# 15-MT7688AN_Ethernet-E.net
KiCad netlist of a schematic drawn in Altium Designer
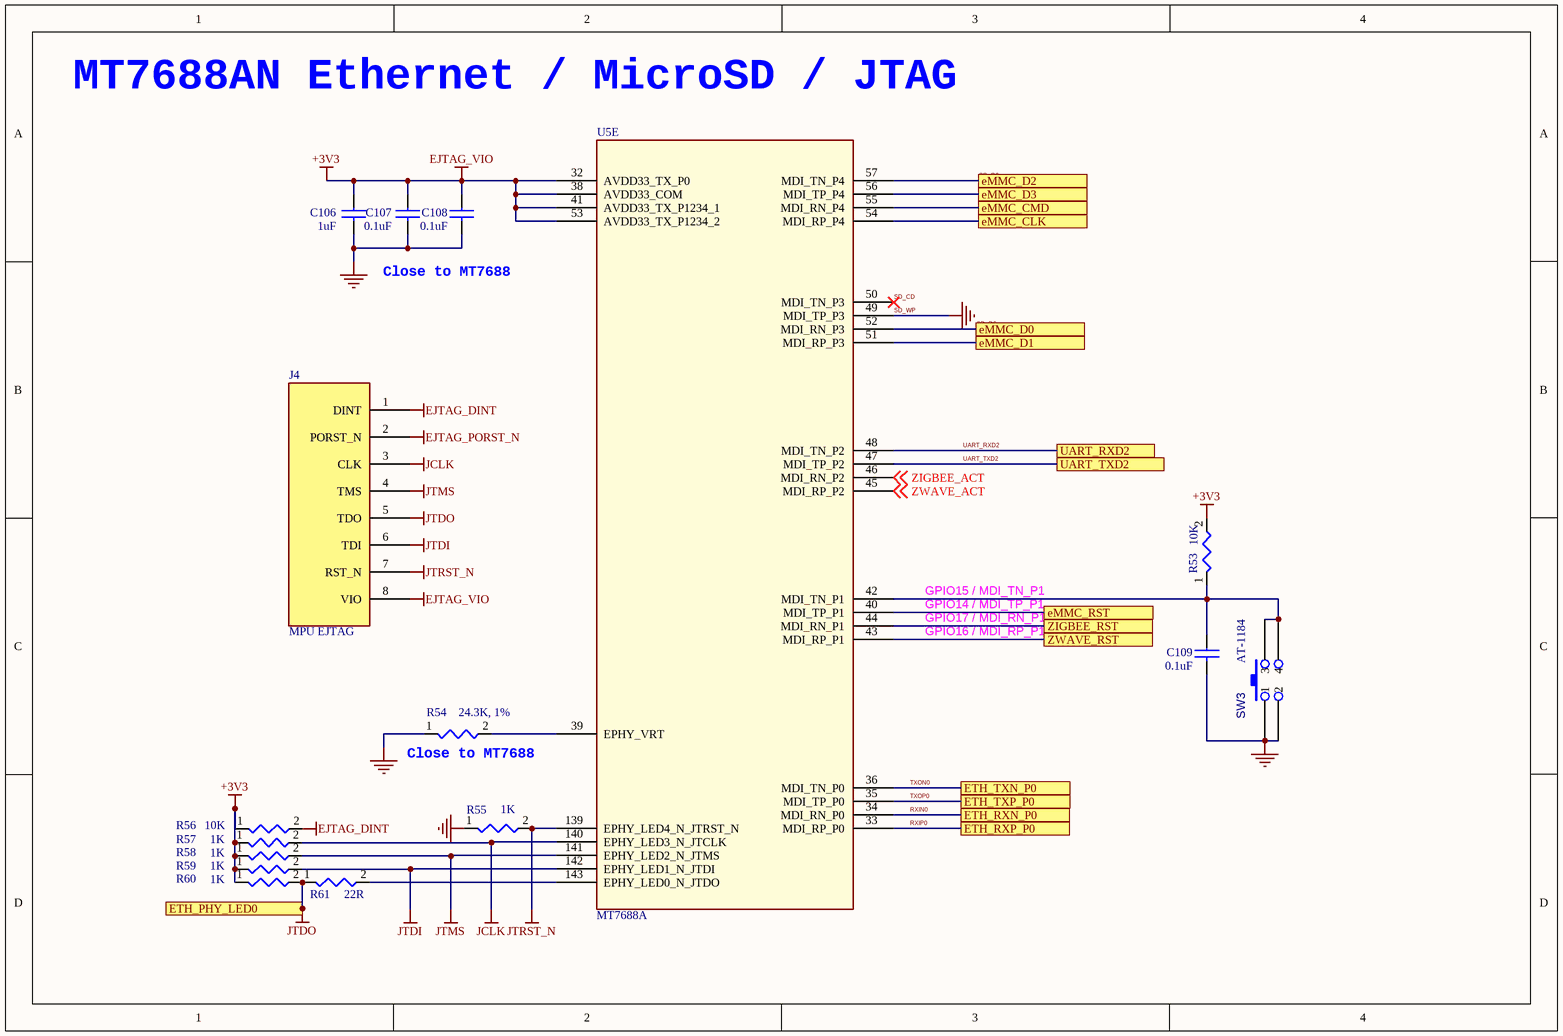
[diagram p0: 15-MT7688AN Ethernet-E.SchDoc]

(export (version "E")
  (design (tool "Eeschema 10.0.6"))
  (components
    (comp (ref "C106")
      (value "1uF")
      (footprint "CAPC1005X60X30NL05T10")
      (libsource (lib "MT7688AN") (part "CAP NP"))
    )
    (comp (ref "C107")
      (value "0.1uF")
      (footprint "CAPC1005X60X30NL05T10")
      (libsource (lib "MT7688AN") (part "CAP NP"))
    )
    (comp (ref "C108")
      (value "0.1uF")
      (footprint "CAPC1005X60X30NL05T10")
      (libsource (lib "MT7688AN") (part "CAP NP"))
    )
    (comp (ref "C109")
      (value "0.1uF")
      (footprint "CAPC1005X60X30NL05T10")
      (libsource (lib "MT7688AN") (part "CAP NP"))
    )
    (comp (ref "J4")
      (value "MPU EJTAG")
      (footprint "MPU EJTAG DEBUG")
      (libsource (lib "MT7688AN") (part "MPU EJTAG"))
    )
    (comp (ref "R53")
      (value "10K")
      (footprint "RESC1005X35X25NL10T10")
      (libsource (lib "MT7688AN") (part "RES/0402_3"))
    )
    (comp (ref "R54")
      (value "24.3K, 1%")
      (footprint "RESC1005X35X25NL10T10")
      (libsource (lib "MT7688AN") (part "RES/0402_3"))
    )
    (comp (ref "R55")
      (value "1K")
      (footprint "RESC1005X35X25NL10T10")
      (libsource (lib "MT7688AN") (part "RES/0402_3"))
    )
    (comp (ref "R56")
      (value "10K")
      (footprint "RESC1005X35X25NL10T10")
      (libsource (lib "MT7688AN") (part "RES/0402_3"))
    )
    (comp (ref "R57")
      (value "1K")
      (footprint "RESC1005X35X25NL10T10")
      (libsource (lib "MT7688AN") (part "RES/0402_3"))
    )
    (comp (ref "R58")
      (value "1K")
      (footprint "RESC1005X35X25NL10T10")
      (libsource (lib "MT7688AN") (part "RES/0402_3"))
    )
    (comp (ref "R59")
      (value "1K")
      (footprint "RESC1005X35X25NL10T10")
      (libsource (lib "MT7688AN") (part "RES/0402_3"))
    )
    (comp (ref "R60")
      (value "1K")
      (footprint "RESC1005X35X25NL10T10")
      (libsource (lib "MT7688AN") (part "RES/0402_3"))
    )
    (comp (ref "R61")
      (value "22R")
      (footprint "RESC1005X35X25NL10T10")
      (libsource (lib "MT7688AN") (part "RES/0402_3"))
    )
    (comp (ref "SW3")
      (value "AT-1184")
      (footprint "AT-1184 SW")
      (description "TACT Switch, H=1.5mm")
      (fields (field (name "MANUFACTURER") "Panasonic - ECG"))
      (libsource (lib "MT7688AN") (part "SW"))
    )
    (comp (ref "U5")
      (value "MT7688A")
      (footprint "MT7628AN$2F$DRQFN156$2F$SMD$2F$P0.5$2F$12X12")
      (libsource (lib "MT7688AN") (part "MT7620N-n_26"))
    )
  )
  (nets
    (net (code "1") (name "+3V3") (class "Default")
      (node (ref "C106") (pin "1") (pinfunction "1_1") (pintype "passive"))
      (node (ref "C107") (pin "1") (pinfunction "1_1") (pintype "passive"))
      (node (ref "C108") (pin "1") (pinfunction "1_1") (pintype "passive"))
      (node (ref "J4") (pin "8") (pinfunction "VIO_8") (pintype "passive"))
      (node (ref "R53") (pin "2") (pinfunction "2_2") (pintype "passive"))
      (node (ref "R56") (pin "1") (pinfunction "1_1") (pintype "passive"))
      (node (ref "R57") (pin "1") (pinfunction "1_1") (pintype "passive"))
      (node (ref "R58") (pin "1") (pinfunction "1_1") (pintype "passive"))
      (node (ref "R59") (pin "1") (pinfunction "1_1") (pintype "passive"))
      (node (ref "R60") (pin "1") (pinfunction "1_1") (pintype "passive"))
      (node (ref "U5") (pin "32") (pinfunction "AVDD33_TX_P0_32") (pintype "power_in"))
      (node (ref "U5") (pin "38") (pinfunction "AVDD33_COM_38") (pintype "power_in"))
      (node (ref "U5") (pin "41") (pinfunction "AVDD33_TX_P1234_1_41") (pintype "power_in"))
      (node (ref "U5") (pin "53") (pinfunction "AVDD33_TX_P1234_2_53") (pintype "power_in"))
    )
    (net (code "2") (name "/GPIO14 {slash} MDI_TP_P1") (class "Default")
      (node (ref "U5") (pin "40") (pinfunction "MDI_TP_P1_40") (pintype "passive"))
    )
    (net (code "3") (name "/GPIO15 {slash} MDI_TN_P1") (class "Default")
      (node (ref "C109") (pin "1") (pinfunction "1_1") (pintype "passive"))
      (node (ref "R53") (pin "1") (pinfunction "1_1") (pintype "passive"))
      (node (ref "SW3") (pin "3") (pinfunction "3_3") (pintype "passive"))
      (node (ref "SW3") (pin "4") (pinfunction "4_4") (pintype "passive"))
      (node (ref "U5") (pin "42") (pinfunction "MDI_TN_P1_42") (pintype "passive"))
    )
    (net (code "4") (name "/GPIO16 {slash} MDI_RP_P1") (class "Default")
      (node (ref "U5") (pin "43") (pinfunction "MDI_RP_P1_43") (pintype "passive"))
    )
    (net (code "5") (name "/GPIO17 {slash} MDI_RN_P1") (class "Default")
      (node (ref "U5") (pin "44") (pinfunction "MDI_RN_P1_44") (pintype "passive"))
    )
    (net (code "6") (name "/RXIN0") (class "Default")
      (node (ref "U5") (pin "34") (pinfunction "MDI_RN_P0_34") (pintype "passive"))
    )
    (net (code "7") (name "/RXIP0") (class "Default")
      (node (ref "U5") (pin "33") (pinfunction "MDI_RP_P0_33") (pintype "passive"))
    )
    (net (code "8") (name "/SD_CD") (class "Default")
      (node (ref "U5") (pin "50") (pinfunction "MDI_TN_P3_50") (pintype "passive+no_connect"))
    )
    (net (code "9") (name "/SD_CLK") (class "Default")
      (node (ref "U5") (pin "54") (pinfunction "MDI_RP_P4_54") (pintype "passive"))
    )
    (net (code "10") (name "/SD_CMD") (class "Default")
      (node (ref "U5") (pin "55") (pinfunction "MDI_RN_P4_55") (pintype "passive"))
    )
    (net (code "11") (name "/SD_D0") (class "Default")
      (node (ref "U5") (pin "52") (pinfunction "MDI_RN_P3_52") (pintype "passive"))
    )
    (net (code "12") (name "/SD_D1") (class "Default")
      (node (ref "U5") (pin "51") (pinfunction "MDI_RP_P3_51") (pintype "passive"))
    )
    (net (code "13") (name "/SD_D2") (class "Default")
      (node (ref "U5") (pin "57") (pinfunction "MDI_TN_P4_57") (pintype "passive"))
    )
    (net (code "14") (name "/SD_D3") (class "Default")
      (node (ref "U5") (pin "56") (pinfunction "MDI_TP_P4_56") (pintype "passive"))
    )
    (net (code "15") (name "/TXON0") (class "Default")
      (node (ref "U5") (pin "36") (pinfunction "MDI_TN_P0_36") (pintype "passive"))
    )
    (net (code "16") (name "/TXOP0") (class "Default")
      (node (ref "U5") (pin "35") (pinfunction "MDI_TP_P0_35") (pintype "passive"))
    )
    (net (code "17") (name "/UART_RXD2") (class "Default")
      (node (ref "U5") (pin "48") (pinfunction "MDI_TN_P2_48") (pintype "passive"))
    )
    (net (code "18") (name "/UART_TXD2") (class "Default")
      (node (ref "U5") (pin "47") (pinfunction "MDI_TP_P2_47") (pintype "passive"))
    )
    (net (code "19") (name "EJTAG_DINT") (class "Default")
      (node (ref "J4") (pin "1") (pinfunction "DINT_1") (pintype "passive"))
      (node (ref "R56") (pin "2") (pinfunction "2_2") (pintype "passive"))
    )
    (net (code "20") (name "EJTAG_PORST_N") (class "Default")
      (node (ref "J4") (pin "2") (pinfunction "PORST_N_2") (pintype "passive"))
    )
    (net (code "21") (name "GND") (class "Default")
      (node (ref "C106") (pin "2") (pinfunction "2_2") (pintype "passive"))
      (node (ref "C107") (pin "2") (pinfunction "2_2") (pintype "passive"))
      (node (ref "C108") (pin "2") (pinfunction "2_2") (pintype "passive"))
      (node (ref "C109") (pin "2") (pinfunction "2_2") (pintype "passive"))
      (node (ref "R54") (pin "1") (pinfunction "1_1") (pintype "passive"))
      (node (ref "R55") (pin "1") (pinfunction "1_1") (pintype "passive"))
      (node (ref "SW3") (pin "1") (pinfunction "1_1") (pintype "passive"))
      (node (ref "SW3") (pin "2") (pinfunction "2_2") (pintype "passive"))
      (node (ref "U5") (pin "49") (pinfunction "MDI_TP_P3_49") (pintype "passive"))
    )
    (net (code "22") (name "JCLK") (class "Default")
      (node (ref "J4") (pin "3") (pinfunction "CLK_3") (pintype "passive"))
      (node (ref "R57") (pin "2") (pinfunction "2_2") (pintype "passive"))
      (node (ref "U5") (pin "140") (pinfunction "EPHY_LED3_N_JTCLK_140") (pintype "passive"))
    )
    (net (code "23") (name "JTDI") (class "Default")
      (node (ref "J4") (pin "6") (pinfunction "TDI_6") (pintype "passive"))
      (node (ref "R59") (pin "2") (pinfunction "2_2") (pintype "passive"))
      (node (ref "U5") (pin "142") (pinfunction "EPHY_LED1_N_JTDI_142") (pintype "passive"))
    )
    (net (code "24") (name "JTDO") (class "Default")
      (node (ref "J4") (pin "5") (pinfunction "TDO_5") (pintype "passive"))
      (node (ref "R60") (pin "2") (pinfunction "2_2") (pintype "passive"))
      (node (ref "R61") (pin "1") (pinfunction "1_1") (pintype "passive"))
    )
    (net (code "25") (name "JTMS") (class "Default")
      (node (ref "J4") (pin "4") (pinfunction "TMS_4") (pintype "passive"))
      (node (ref "R58") (pin "2") (pinfunction "2_2") (pintype "passive"))
      (node (ref "U5") (pin "141") (pinfunction "EPHY_LED2_N_JTMS_141") (pintype "passive"))
    )
    (net (code "26") (name "JTRST_N") (class "Default")
      (node (ref "J4") (pin "7") (pinfunction "RST_N_7") (pintype "passive"))
      (node (ref "R55") (pin "2") (pinfunction "2_2") (pintype "passive"))
      (node (ref "U5") (pin "139") (pinfunction "EPHY_LED4_N_JTRST_N_139") (pintype "passive"))
    )
    (net (code "27") (name "Net-(U5E-EPHY_LED0_N_JTDO)") (class "Default")
      (node (ref "R61") (pin "2") (pinfunction "2_2") (pintype "passive"))
      (node (ref "U5") (pin "143") (pinfunction "EPHY_LED0_N_JTDO_143") (pintype "passive"))
    )
    (net (code "28") (name "Net-(U5E-EPHY_VRT)") (class "Default")
      (node (ref "R54") (pin "2") (pinfunction "2_2") (pintype "passive"))
      (node (ref "U5") (pin "39") (pinfunction "EPHY_VRT_39") (pintype "passive"))
    )
    (net (code "29") (name "ZIGBEE_ACT") (class "Default")
      (node (ref "U5") (pin "46") (pinfunction "MDI_RN_P2_46") (pintype "passive"))
    )
    (net (code "30") (name "ZWAVE_ACT") (class "Default")
      (node (ref "U5") (pin "45") (pinfunction "MDI_RP_P2_45") (pintype "passive"))
    )
  )
)
